# IMU.net
KiCad netlist of a schematic drawn in Altium Designer
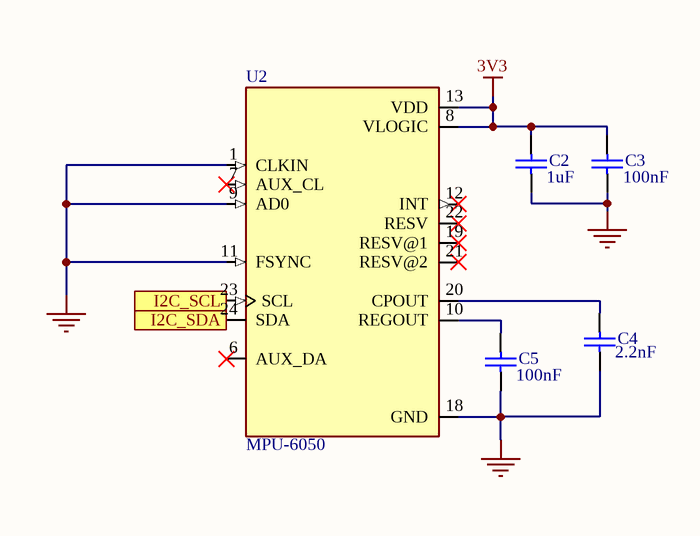
[diagram p0: IMU.SchDoc]

(export (version "E")
  (design (tool "Eeschema 10.0.6"))
  (components
    (comp (ref "C2")
      (value "1uF")
      (footprint "0402")
      (fields (field (name "Comment") "Cap") (field (name "PUBLISHER") "Altium Limited"))
      (libsource (lib "Parts") (part "Cap"))
    )
    (comp (ref "C3")
      (value "100nF")
      (footprint "0402")
      (fields (field (name "Comment") "Cap") (field (name "PUBLISHER") "Altium Limited"))
      (libsource (lib "Parts") (part "Cap"))
    )
    (comp (ref "C4")
      (value "2.2nF")
      (footprint "0402")
      (fields (field (name "Comment") "Cap") (field (name "PUBLISHER") "Altium Limited"))
      (libsource (lib "Parts") (part "Cap"))
    )
    (comp (ref "C5")
      (value "100nF")
      (footprint "0402")
      (fields (field (name "Comment") "Cap") (field (name "PUBLISHER") "Altium Limited"))
      (libsource (lib "Parts") (part "Cap"))
    )
    (comp (ref "U2")
      (value "MPU-6050")
      (footprint "QFN50P400X400X95-24N")
      (description "Accelerometer, Gyroscope, 6 Axis Sensor IÂ²C Output")
      (fields (field (name "MF") "TDK InvenSense"))
      (libsource (lib "Parts") (part "MPU-6050"))
    )
  )
  (nets
    (net (code "1") (name "/I2C_SCL") (class "Default")
      (node (ref "U2") (pin "23") (pinfunction "SCL_23") (pintype "input"))
    )
    (net (code "2") (name "/I2C_SDA") (class "Default")
      (node (ref "U2") (pin "24") (pinfunction "SDA_24") (pintype "bidirectional"))
    )
    (net (code "3") (name "3V3") (class "Default")
      (node (ref "C2") (pin "2") (pinfunction "2_2") (pintype "passive"))
      (node (ref "C3") (pin "2") (pinfunction "2_2") (pintype "passive"))
      (node (ref "U2") (pin "13") (pinfunction "VDD_13") (pintype "power_in"))
      (node (ref "U2") (pin "8") (pinfunction "VLOGIC_8") (pintype "power_in"))
    )
    (net (code "4") (name "GND") (class "Default")
      (node (ref "C2") (pin "1") (pinfunction "1_1") (pintype "passive"))
      (node (ref "C3") (pin "1") (pinfunction "1_1") (pintype "passive"))
      (node (ref "C4") (pin "1") (pinfunction "1_1") (pintype "passive"))
      (node (ref "C5") (pin "1") (pinfunction "1_1") (pintype "passive"))
      (node (ref "U2") (pin "1") (pinfunction "CLKIN_1") (pintype "input"))
      (node (ref "U2") (pin "11") (pinfunction "FSYNC_11") (pintype "input"))
      (node (ref "U2") (pin "18") (pinfunction "GND_18") (pintype "power_in"))
      (node (ref "U2") (pin "9") (pinfunction "AD0_9") (pintype "input"))
    )
    (net (code "5") (name "Net-(U2-CPOUT)") (class "Default")
      (node (ref "C4") (pin "2") (pinfunction "2_2") (pintype "passive"))
      (node (ref "U2") (pin "20") (pinfunction "CPOUT_20") (pintype "passive"))
    )
    (net (code "6") (name "Net-(U2-REGOUT)") (class "Default")
      (node (ref "C5") (pin "2") (pinfunction "2_2") (pintype "passive"))
      (node (ref "U2") (pin "10") (pinfunction "REGOUT_10") (pintype "passive"))
    )
    (net (code "7") (name "unconnected-(U2-AUX_CL-Pad7)") (class "Default")
      (node (ref "U2") (pin "7") (pinfunction "AUX_CL_7") (pintype "input+no_connect"))
    )
    (net (code "8") (name "unconnected-(U2-AUX_DA-Pad6)") (class "Default")
      (node (ref "U2") (pin "6") (pinfunction "AUX_DA_6") (pintype "bidirectional+no_connect"))
    )
    (net (code "9") (name "unconnected-(U2-INT-Pad12)") (class "Default")
      (node (ref "U2") (pin "12") (pinfunction "INT_12") (pintype "output+no_connect"))
    )
    (net (code "10") (name "unconnected-(U2-RESV-Pad22)") (class "Default")
      (node (ref "U2") (pin "22") (pinfunction "RESV_22") (pintype "passive+no_connect"))
    )
    (net (code "11") (name "unconnected-(U2-RESV@1-Pad19)") (class "Default")
      (node (ref "U2") (pin "19") (pinfunction "RESV@1_19") (pintype "passive+no_connect"))
    )
    (net (code "12") (name "unconnected-(U2-RESV@2-Pad21)") (class "Default")
      (node (ref "U2") (pin "21") (pinfunction "RESV@2_21") (pintype "passive+no_connect"))
    )
  )
)
